# S7CAS-PLEIADES-CARTE-MERE_P06_DDR3.net
KiCad netlist of a schematic drawn in Altium Designer
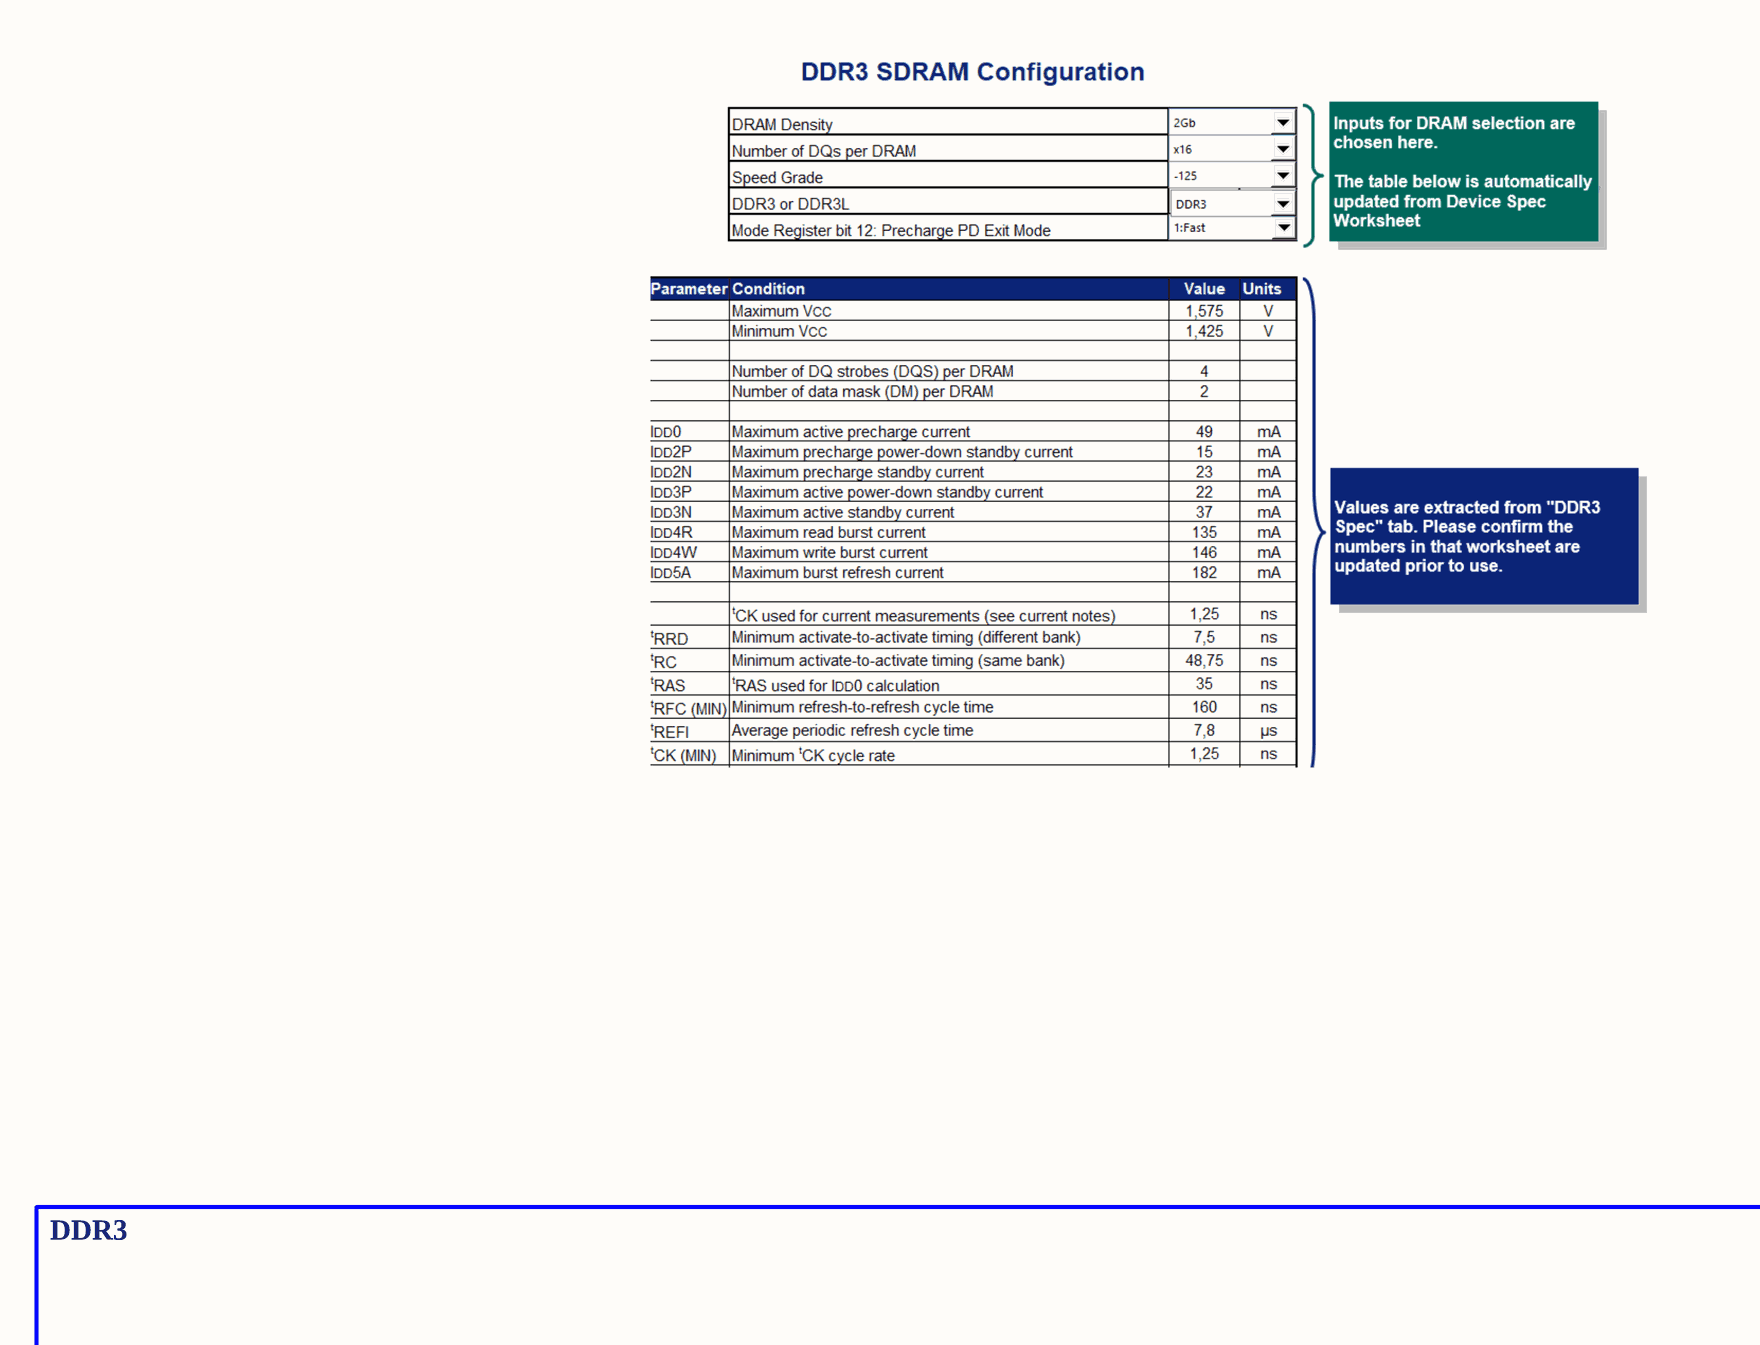
[diagram p0: S7CAS-PLEIADES-CARTE-MERE_P06_DDR3.SCHDOC, top left]
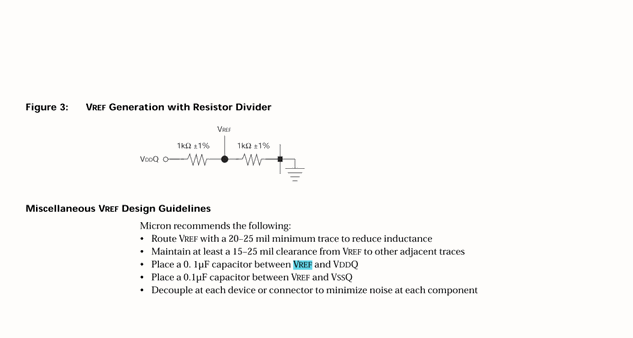
[diagram p1: S7CAS-PLEIADES-CARTE-MERE_P06_DDR3.SCHDOC, top right]
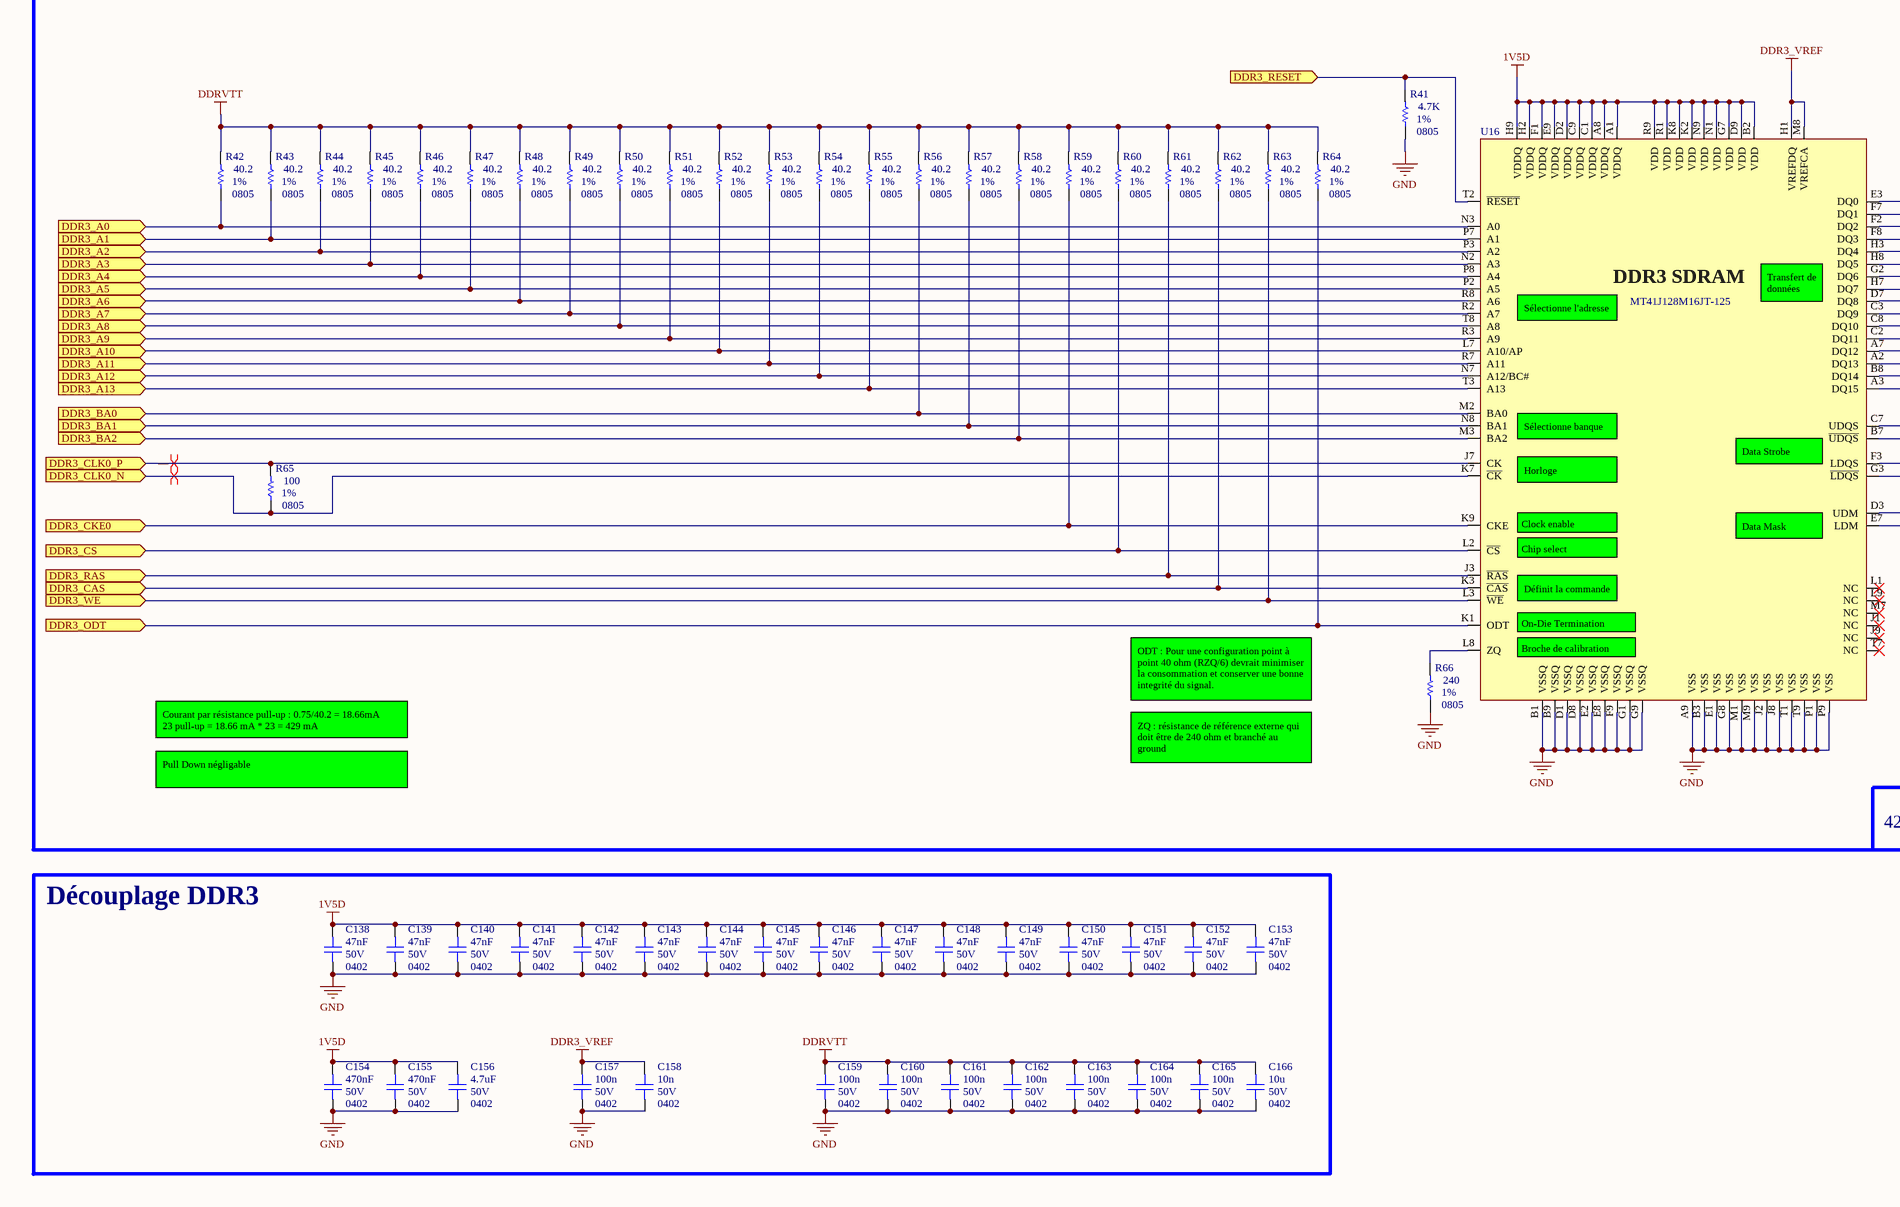
[diagram p2: S7CAS-PLEIADES-CARTE-MERE_P06_DDR3.SCHDOC, bottom left]
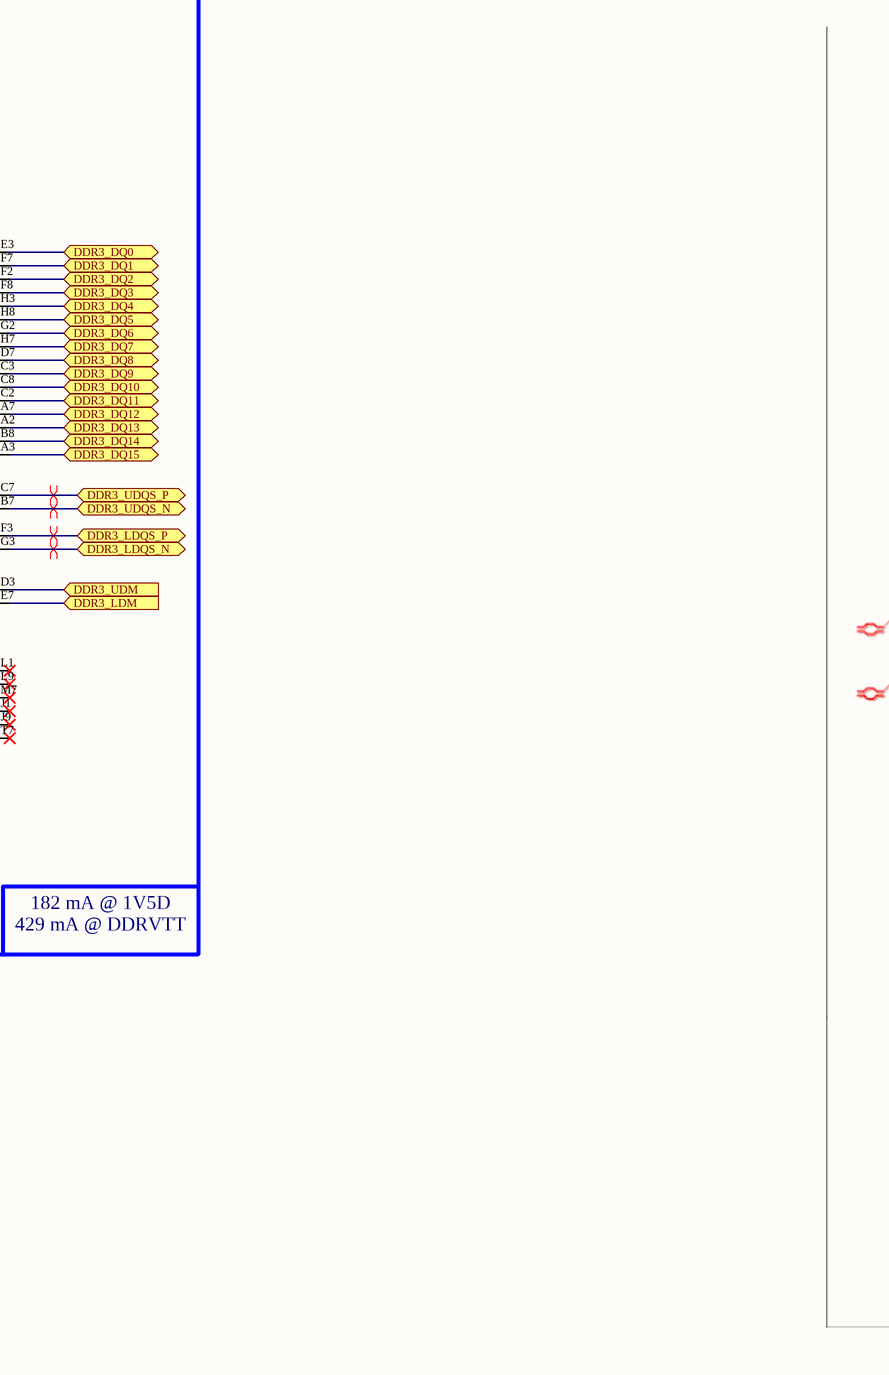
[diagram p3: S7CAS-PLEIADES-CARTE-MERE_P06_DDR3.SCHDOC, bottom middle]
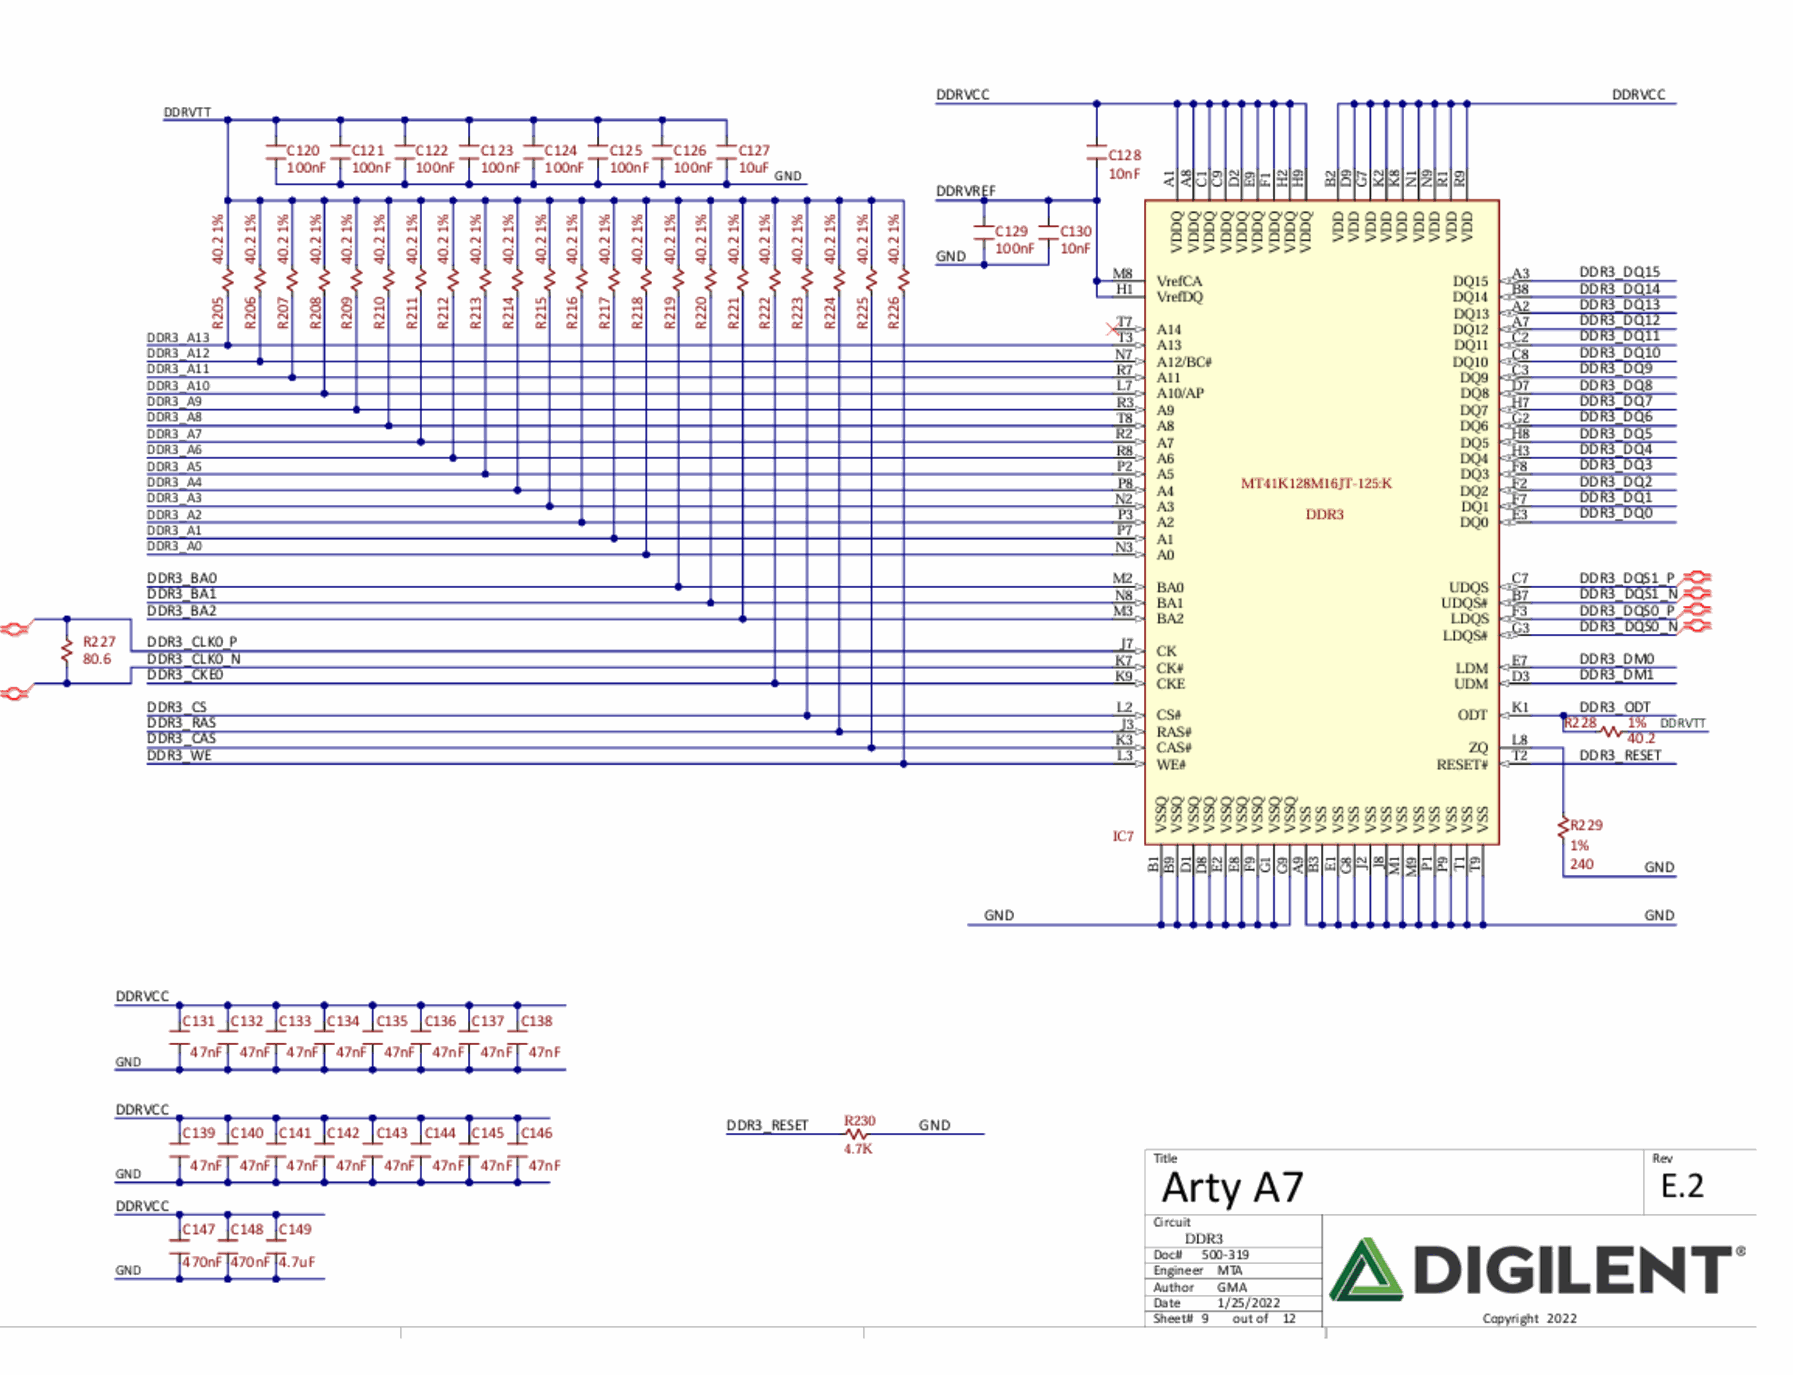
[diagram p4: S7CAS-PLEIADES-CARTE-MERE_P06_DDR3.SCHDOC, bottom right]

(export (version "E")
  (design (tool "Eeschema 10.0.6"))
  (components
    (comp (ref "C138")
      (value "47nF")
      (footprint "CAP_0402")
      (description "CAP - 0402")
      (fields
        (field (name "VOLTAGE") "50V")
        (field (name "PACKAGE") "0402")
        (field (name "CREATEDBY") "Jonathan Bouchard")
      )
      (libsource (lib "s7cas_lib2023") (part "CAP - 0402"))
    )
    (comp (ref "C139")
      (value "47nF")
      (footprint "CAP_0402")
      (description "CAP - 0402")
      (fields
        (field (name "VOLTAGE") "50V")
        (field (name "PACKAGE") "0402")
        (field (name "CREATEDBY") "Jonathan Bouchard")
      )
      (libsource (lib "s7cas_lib2023") (part "CAP - 0402"))
    )
    (comp (ref "C140")
      (value "47nF")
      (footprint "CAP_0402")
      (description "CAP - 0402")
      (fields
        (field (name "VOLTAGE") "50V")
        (field (name "PACKAGE") "0402")
        (field (name "CREATEDBY") "Jonathan Bouchard")
      )
      (libsource (lib "s7cas_lib2023") (part "CAP - 0402"))
    )
    (comp (ref "C141")
      (value "47nF")
      (footprint "CAP_0402")
      (description "CAP - 0402")
      (fields
        (field (name "VOLTAGE") "50V")
        (field (name "PACKAGE") "0402")
        (field (name "CREATEDBY") "Jonathan Bouchard")
      )
      (libsource (lib "s7cas_lib2023") (part "CAP - 0402"))
    )
    (comp (ref "C142")
      (value "47nF")
      (footprint "CAP_0402")
      (description "CAP - 0402")
      (fields
        (field (name "VOLTAGE") "50V")
        (field (name "PACKAGE") "0402")
        (field (name "CREATEDBY") "Jonathan Bouchard")
      )
      (libsource (lib "s7cas_lib2023") (part "CAP - 0402"))
    )
    (comp (ref "C143")
      (value "47nF")
      (footprint "CAP_0402")
      (description "CAP - 0402")
      (fields
        (field (name "VOLTAGE") "50V")
        (field (name "PACKAGE") "0402")
        (field (name "CREATEDBY") "Jonathan Bouchard")
      )
      (libsource (lib "s7cas_lib2023") (part "CAP - 0402"))
    )
    (comp (ref "C144")
      (value "47nF")
      (footprint "CAP_0402")
      (description "CAP - 0402")
      (fields
        (field (name "VOLTAGE") "50V")
        (field (name "PACKAGE") "0402")
        (field (name "CREATEDBY") "Jonathan Bouchard")
      )
      (libsource (lib "s7cas_lib2023") (part "CAP - 0402"))
    )
    (comp (ref "C145")
      (value "47nF")
      (footprint "CAP_0402")
      (description "CAP - 0402")
      (fields
        (field (name "VOLTAGE") "50V")
        (field (name "PACKAGE") "0402")
        (field (name "CREATEDBY") "Jonathan Bouchard")
      )
      (libsource (lib "s7cas_lib2023") (part "CAP - 0402"))
    )
    (comp (ref "C146")
      (value "47nF")
      (footprint "CAP_0402")
      (description "CAP - 0402")
      (fields
        (field (name "VOLTAGE") "50V")
        (field (name "PACKAGE") "0402")
        (field (name "CREATEDBY") "Jonathan Bouchard")
      )
      (libsource (lib "s7cas_lib2023") (part "CAP - 0402"))
    )
    (comp (ref "C147")
      (value "47nF")
      (footprint "CAP_0402")
      (description "CAP - 0402")
      (fields
        (field (name "VOLTAGE") "50V")
        (field (name "PACKAGE") "0402")
        (field (name "CREATEDBY") "Jonathan Bouchard")
      )
      (libsource (lib "s7cas_lib2023") (part "CAP - 0402"))
    )
    (comp (ref "C148")
      (value "47nF")
      (footprint "CAP_0402")
      (description "CAP - 0402")
      (fields
        (field (name "VOLTAGE") "50V")
        (field (name "PACKAGE") "0402")
        (field (name "CREATEDBY") "Jonathan Bouchard")
      )
      (libsource (lib "s7cas_lib2023") (part "CAP - 0402"))
    )
    (comp (ref "C149")
      (value "47nF")
      (footprint "CAP_0402")
      (description "CAP - 0402")
      (fields
        (field (name "VOLTAGE") "50V")
        (field (name "PACKAGE") "0402")
        (field (name "CREATEDBY") "Jonathan Bouchard")
      )
      (libsource (lib "s7cas_lib2023") (part "CAP - 0402"))
    )
    (comp (ref "C150")
      (value "47nF")
      (footprint "CAP_0402")
      (description "CAP - 0402")
      (fields
        (field (name "VOLTAGE") "50V")
        (field (name "PACKAGE") "0402")
        (field (name "CREATEDBY") "Jonathan Bouchard")
      )
      (libsource (lib "s7cas_lib2023") (part "CAP - 0402"))
    )
    (comp (ref "C151")
      (value "47nF")
      (footprint "CAP_0402")
      (description "CAP - 0402")
      (fields
        (field (name "VOLTAGE") "50V")
        (field (name "PACKAGE") "0402")
        (field (name "CREATEDBY") "Jonathan Bouchard")
      )
      (libsource (lib "s7cas_lib2023") (part "CAP - 0402"))
    )
    (comp (ref "C152")
      (value "47nF")
      (footprint "CAP_0402")
      (description "CAP - 0402")
      (fields
        (field (name "VOLTAGE") "50V")
        (field (name "PACKAGE") "0402")
        (field (name "CREATEDBY") "Jonathan Bouchard")
      )
      (libsource (lib "s7cas_lib2023") (part "CAP - 0402"))
    )
    (comp (ref "C153")
      (value "47nF")
      (footprint "CAP_0402")
      (description "CAP - 0402")
      (fields
        (field (name "VOLTAGE") "50V")
        (field (name "PACKAGE") "0402")
        (field (name "CREATEDBY") "Jonathan Bouchard")
      )
      (libsource (lib "s7cas_lib2023") (part "CAP - 0402"))
    )
    (comp (ref "C154")
      (value "470nF")
      (footprint "CAP_0402")
      (description "CAP - 0402")
      (fields
        (field (name "VOLTAGE") "50V")
        (field (name "PACKAGE") "0402")
        (field (name "CREATEDBY") "Jonathan Bouchard")
      )
      (libsource (lib "s7cas_lib2023") (part "CAP - 0402"))
    )
    (comp (ref "C155")
      (value "470nF")
      (footprint "CAP_0402")
      (description "CAP - 0402")
      (fields
        (field (name "VOLTAGE") "50V")
        (field (name "PACKAGE") "0402")
        (field (name "CREATEDBY") "Jonathan Bouchard")
      )
      (libsource (lib "s7cas_lib2023") (part "CAP - 0402"))
    )
    (comp (ref "C156")
      (value "4.7uF")
      (footprint "CAP_0402")
      (description "CAP - 0402")
      (fields
        (field (name "VOLTAGE") "50V")
        (field (name "PACKAGE") "0402")
        (field (name "CREATEDBY") "Jonathan Bouchard")
      )
      (libsource (lib "s7cas_lib2023") (part "CAP - 0402"))
    )
    (comp (ref "C157")
      (value "100n")
      (footprint "CAP_0402")
      (description "CAP - 0402")
      (fields
        (field (name "VOLTAGE") "50V")
        (field (name "PACKAGE") "0402")
        (field (name "CREATEDBY") "Jonathan Bouchard")
      )
      (libsource (lib "s7cas_lib2023") (part "CAP - 0402"))
    )
    (comp (ref "C158")
      (value "10n")
      (footprint "CAP_0402")
      (description "CAP - 0402")
      (fields
        (field (name "VOLTAGE") "50V")
        (field (name "PACKAGE") "0402")
        (field (name "CREATEDBY") "Jonathan Bouchard")
      )
      (libsource (lib "s7cas_lib2023") (part "CAP - 0402"))
    )
    (comp (ref "C159")
      (value "100n")
      (footprint "CAP_0402")
      (description "CAP - 0402")
      (fields
        (field (name "VOLTAGE") "50V")
        (field (name "PACKAGE") "0402")
        (field (name "CREATEDBY") "Jonathan Bouchard")
      )
      (libsource (lib "s7cas_lib2023") (part "CAP - 0402"))
    )
    (comp (ref "C160")
      (value "100n")
      (footprint "CAP_0402")
      (description "CAP - 0402")
      (fields
        (field (name "VOLTAGE") "50V")
        (field (name "PACKAGE") "0402")
        (field (name "CREATEDBY") "Jonathan Bouchard")
      )
      (libsource (lib "s7cas_lib2023") (part "CAP - 0402"))
    )
    (comp (ref "C161")
      (value "100n")
      (footprint "CAP_0402")
      (description "CAP - 0402")
      (fields
        (field (name "VOLTAGE") "50V")
        (field (name "PACKAGE") "0402")
        (field (name "CREATEDBY") "Jonathan Bouchard")
      )
      (libsource (lib "s7cas_lib2023") (part "CAP - 0402"))
    )
    (comp (ref "C162")
      (value "100n")
      (footprint "CAP_0402")
      (description "CAP - 0402")
      (fields
        (field (name "VOLTAGE") "50V")
        (field (name "PACKAGE") "0402")
        (field (name "CREATEDBY") "Jonathan Bouchard")
      )
      (libsource (lib "s7cas_lib2023") (part "CAP - 0402"))
    )
    (comp (ref "C163")
      (value "100n")
      (footprint "CAP_0402")
      (description "CAP - 0402")
      (fields
        (field (name "VOLTAGE") "50V")
        (field (name "PACKAGE") "0402")
        (field (name "CREATEDBY") "Jonathan Bouchard")
      )
      (libsource (lib "s7cas_lib2023") (part "CAP - 0402"))
    )
    (comp (ref "C164")
      (value "100n")
      (footprint "CAP_0402")
      (description "CAP - 0402")
      (fields
        (field (name "VOLTAGE") "50V")
        (field (name "PACKAGE") "0402")
        (field (name "CREATEDBY") "Jonathan Bouchard")
      )
      (libsource (lib "s7cas_lib2023") (part "CAP - 0402"))
    )
    (comp (ref "C165")
      (value "100n")
      (footprint "CAP_0402")
      (description "CAP - 0402")
      (fields
        (field (name "VOLTAGE") "50V")
        (field (name "PACKAGE") "0402")
        (field (name "CREATEDBY") "Jonathan Bouchard")
      )
      (libsource (lib "s7cas_lib2023") (part "CAP - 0402"))
    )
    (comp (ref "C166")
      (value "10u")
      (footprint "CAP_0402")
      (description "CAP - 0402")
      (fields
        (field (name "VOLTAGE") "50V")
        (field (name "PACKAGE") "0402")
        (field (name "CREATEDBY") "Jonathan Bouchard")
      )
      (libsource (lib "s7cas_lib2023") (part "CAP - 0402"))
    )
    (comp (ref "R41")
      (value "4.7K")
      (footprint "RES_0805")
      (description "RES - 0805")
      (fields
        (field (name "PACKAGE") "0805")
        (field (name "PRECISION") "1%")
        (field (name "CREATEDBY") "Jonathan Bouchard")
      )
      (libsource (lib "s7cas_lib2023") (part "RES - 0805"))
    )
    (comp (ref "R42")
      (value "40.2")
      (footprint "RES_0805")
      (description "RES - 0805")
      (fields
        (field (name "PACKAGE") "0805")
        (field (name "PRECISION") "1%")
        (field (name "CREATEDBY") "Jonathan Bouchard")
      )
      (libsource (lib "s7cas_lib2023") (part "RES - 0805"))
    )
    (comp (ref "R43")
      (value "40.2")
      (footprint "RES_0805")
      (description "RES - 0805")
      (fields
        (field (name "PACKAGE") "0805")
        (field (name "PRECISION") "1%")
        (field (name "CREATEDBY") "Jonathan Bouchard")
      )
      (libsource (lib "s7cas_lib2023") (part "RES - 0805"))
    )
    (comp (ref "R44")
      (value "40.2")
      (footprint "RES_0805")
      (description "RES - 0805")
      (fields
        (field (name "PACKAGE") "0805")
        (field (name "PRECISION") "1%")
        (field (name "CREATEDBY") "Jonathan Bouchard")
      )
      (libsource (lib "s7cas_lib2023") (part "RES - 0805"))
    )
    (comp (ref "R45")
      (value "40.2")
      (footprint "RES_0805")
      (description "RES - 0805")
      (fields
        (field (name "PACKAGE") "0805")
        (field (name "PRECISION") "1%")
        (field (name "CREATEDBY") "Jonathan Bouchard")
      )
      (libsource (lib "s7cas_lib2023") (part "RES - 0805"))
    )
    (comp (ref "R46")
      (value "40.2")
      (footprint "RES_0805")
      (description "RES - 0805")
      (fields
        (field (name "PACKAGE") "0805")
        (field (name "PRECISION") "1%")
        (field (name "CREATEDBY") "Jonathan Bouchard")
      )
      (libsource (lib "s7cas_lib2023") (part "RES - 0805"))
    )
    (comp (ref "R47")
      (value "40.2")
      (footprint "RES_0805")
      (description "RES - 0805")
      (fields
        (field (name "PACKAGE") "0805")
        (field (name "PRECISION") "1%")
        (field (name "CREATEDBY") "Jonathan Bouchard")
      )
      (libsource (lib "s7cas_lib2023") (part "RES - 0805"))
    )
    (comp (ref "R48")
      (value "40.2")
      (footprint "RES_0805")
      (description "RES - 0805")
      (fields
        (field (name "PACKAGE") "0805")
        (field (name "PRECISION") "1%")
        (field (name "CREATEDBY") "Jonathan Bouchard")
      )
      (libsource (lib "s7cas_lib2023") (part "RES - 0805"))
    )
    (comp (ref "R49")
      (value "40.2")
      (footprint "RES_0805")
      (description "RES - 0805")
      (fields
        (field (name "PACKAGE") "0805")
        (field (name "PRECISION") "1%")
        (field (name "CREATEDBY") "Jonathan Bouchard")
      )
      (libsource (lib "s7cas_lib2023") (part "RES - 0805"))
    )
    (comp (ref "R50")
      (value "40.2")
      (footprint "RES_0805")
      (description "RES - 0805")
      (fields
        (field (name "PACKAGE") "0805")
        (field (name "PRECISION") "1%")
        (field (name "CREATEDBY") "Jonathan Bouchard")
      )
      (libsource (lib "s7cas_lib2023") (part "RES - 0805"))
    )
    (comp (ref "R51")
      (value "40.2")
      (footprint "RES_0805")
      (description "RES - 0805")
      (fields
        (field (name "PACKAGE") "0805")
        (field (name "PRECISION") "1%")
        (field (name "CREATEDBY") "Jonathan Bouchard")
      )
      (libsource (lib "s7cas_lib2023") (part "RES - 0805"))
    )
    (comp (ref "R52")
      (value "40.2")
      (footprint "RES_0805")
      (description "RES - 0805")
      (fields
        (field (name "PACKAGE") "0805")
        (field (name "PRECISION") "1%")
        (field (name "CREATEDBY") "Jonathan Bouchard")
      )
      (libsource (lib "s7cas_lib2023") (part "RES - 0805"))
    )
    (comp (ref "R53")
      (value "40.2")
      (footprint "RES_0805")
      (description "RES - 0805")
      (fields
        (field (name "PACKAGE") "0805")
        (field (name "PRECISION") "1%")
        (field (name "CREATEDBY") "Jonathan Bouchard")
      )
      (libsource (lib "s7cas_lib2023") (part "RES - 0805"))
    )
    (comp (ref "R54")
      (value "40.2")
      (footprint "RES_0805")
      (description "RES - 0805")
      (fields
        (field (name "PACKAGE") "0805")
        (field (name "PRECISION") "1%")
        (field (name "CREATEDBY") "Jonathan Bouchard")
      )
      (libsource (lib "s7cas_lib2023") (part "RES - 0805"))
    )
    (comp (ref "R55")
      (value "40.2")
      (footprint "RES_0805")
      (description "RES - 0805")
      (fields
        (field (name "PACKAGE") "0805")
        (field (name "PRECISION") "1%")
        (field (name "CREATEDBY") "Jonathan Bouchard")
      )
      (libsource (lib "s7cas_lib2023") (part "RES - 0805"))
    )
    (comp (ref "R56")
      (value "40.2")
      (footprint "RES_0805")
      (description "RES - 0805")
      (fields
        (field (name "PACKAGE") "0805")
        (field (name "PRECISION") "1%")
        (field (name "CREATEDBY") "Jonathan Bouchard")
      )
      (libsource (lib "s7cas_lib2023") (part "RES - 0805"))
    )
    (comp (ref "R57")
      (value "40.2")
      (footprint "RES_0805")
      (description "RES - 0805")
      (fields
        (field (name "PACKAGE") "0805")
        (field (name "PRECISION") "1%")
        (field (name "CREATEDBY") "Jonathan Bouchard")
      )
      (libsource (lib "s7cas_lib2023") (part "RES - 0805"))
    )
    (comp (ref "R58")
      (value "40.2")
      (footprint "RES_0805")
      (description "RES - 0805")
      (fields
        (field (name "PACKAGE") "0805")
        (field (name "PRECISION") "1%")
        (field (name "CREATEDBY") "Jonathan Bouchard")
      )
      (libsource (lib "s7cas_lib2023") (part "RES - 0805"))
    )
    (comp (ref "R59")
      (value "40.2")
      (footprint "RES_0805")
      (description "RES - 0805")
      (fields
        (field (name "PACKAGE") "0805")
        (field (name "PRECISION") "1%")
        (field (name "CREATEDBY") "Jonathan Bouchard")
      )
      (libsource (lib "s7cas_lib2023") (part "RES - 0805"))
    )
    (comp (ref "R60")
      (value "40.2")
      (footprint "RES_0805")
      (description "RES - 0805")
      (fields
        (field (name "PACKAGE") "0805")
        (field (name "PRECISION") "1%")
        (field (name "CREATEDBY") "Jonathan Bouchard")
      )
      (libsource (lib "s7cas_lib2023") (part "RES - 0805"))
    )
    (comp (ref "R61")
      (value "40.2")
      (footprint "RES_0805")
      (description "RES - 0805")
      (fields
        (field (name "PACKAGE") "0805")
        (field (name "PRECISION") "1%")
        (field (name "CREATEDBY") "Jonathan Bouchard")
      )
      (libsource (lib "s7cas_lib2023") (part "RES - 0805"))
    )
    (comp (ref "R62")
      (value "40.2")
      (footprint "RES_0805")
      (description "RES - 0805")
      (fields
        (field (name "PACKAGE") "0805")
        (field (name "PRECISION") "1%")
        (field (name "CREATEDBY") "Jonathan Bouchard")
      )
      (libsource (lib "s7cas_lib2023") (part "RES - 0805"))
    )
    (comp (ref "R63")
      (value "40.2")
      (footprint "RES_0805")
      (description "RES - 0805")
      (fields
        (field (name "PACKAGE") "0805")
        (field (name "PRECISION") "1%")
        (field (name "CREATEDBY") "Jonathan Bouchard")
      )
      (libsource (lib "s7cas_lib2023") (part "RES - 0805"))
    )
    (comp (ref "R64")
      (value "40.2")
      (footprint "RES_0805")
      (description "RES - 0805")
      (fields
        (field (name "PACKAGE") "0805")
        (field (name "PRECISION") "1%")
        (field (name "CREATEDBY") "Jonathan Bouchard")
      )
      (libsource (lib "s7cas_lib2023") (part "RES - 0805"))
    )
    (comp (ref "R65")
      (value "100")
      (footprint "RES_0805")
      (description "RES - 0805")
      (fields
        (field (name "PACKAGE") "0805")
        (field (name "PRECISION") "1%")
        (field (name "CREATEDBY") "Jonathan Bouchard")
      )
      (libsource (lib "s7cas_lib2023") (part "RES - 0805"))
    )
    (comp (ref "R66")
      (value "240")
      (footprint "RES_0805")
      (description "RES - 0805")
      (fields
        (field (name "PACKAGE") "0805")
        (field (name "PRECISION") "1%")
        (field (name "CREATEDBY") "Jonathan Bouchard")
      )
      (libsource (lib "s7cas_lib2023") (part "RES - 0805"))
    )
    (comp (ref "U16")
      (value "MT41J128M16JT-125")
      (footprint "MEM_DDR3_MT41J128M16JT-125")
      (description "MEM - DDR3 SDRAM 2GBIT 800MHZ - TFBGA-96")
      (fields
        (field (name "VOLTAGE") "1.425 V ~ 1.575 V")
        (field (name "MFG") "Micrel")
        (field (name "CREATEDBY") "Jonathan Bouchard")
      )
      (libsource (lib "s7cas_lib2023") (part "MEM_DDR3_MT41J128M16JT-125{colon}K TR"))
    )
  )
  (nets
    (net (code "1") (name "/DDR3_A0") (class "Default")
      (node (ref "R42") (pin "1") (pinfunction "1_1") (pintype "passive"))
      (node (ref "U16") (pin "N3") (pinfunction "A0_N3") (pintype "passive"))
    )
    (net (code "2") (name "/DDR3_A1") (class "Default")
      (node (ref "R43") (pin "1") (pinfunction "1_1") (pintype "passive"))
      (node (ref "U16") (pin "P7") (pinfunction "A1_P7") (pintype "passive"))
    )
    (net (code "3") (name "/DDR3_A2") (class "Default")
      (node (ref "R44") (pin "1") (pinfunction "1_1") (pintype "passive"))
      (node (ref "U16") (pin "P3") (pinfunction "A2_P3") (pintype "passive"))
    )
    (net (code "4") (name "/DDR3_A3") (class "Default")
      (node (ref "R45") (pin "1") (pinfunction "1_1") (pintype "passive"))
      (node (ref "U16") (pin "N2") (pinfunction "A3_N2") (pintype "passive"))
    )
    (net (code "5") (name "/DDR3_A4") (class "Default")
      (node (ref "R46") (pin "1") (pinfunction "1_1") (pintype "passive"))
      (node (ref "U16") (pin "P8") (pinfunction "A4_P8") (pintype "passive"))
    )
    (net (code "6") (name "/DDR3_A5") (class "Default")
      (node (ref "R47") (pin "1") (pinfunction "1_1") (pintype "passive"))
      (node (ref "U16") (pin "P2") (pinfunction "A5_P2") (pintype "passive"))
    )
    (net (code "7") (name "/DDR3_A6") (class "Default")
      (node (ref "R48") (pin "1") (pinfunction "1_1") (pintype "passive"))
      (node (ref "U16") (pin "R8") (pinfunction "A6_R8") (pintype "passive"))
    )
    (net (code "8") (name "/DDR3_A7") (class "Default")
      (node (ref "R49") (pin "1") (pinfunction "1_1") (pintype "passive"))
      (node (ref "U16") (pin "R2") (pinfunction "A7_R2") (pintype "passive"))
    )
    (net (code "9") (name "/DDR3_A8") (class "Default")
      (node (ref "R50") (pin "1") (pinfunction "1_1") (pintype "passive"))
      (node (ref "U16") (pin "T8") (pinfunction "A8_T8") (pintype "passive"))
    )
    (net (code "10") (name "/DDR3_A9") (class "Default")
      (node (ref "R51") (pin "1") (pinfunction "1_1") (pintype "passive"))
      (node (ref "U16") (pin "R3") (pinfunction "A9_R3") (pintype "passive"))
    )
    (net (code "11") (name "/DDR3_A10") (class "Default")
      (node (ref "R52") (pin "1") (pinfunction "1_1") (pintype "passive"))
      (node (ref "U16") (pin "L7") (pinfunction "A10/AP_L7") (pintype "passive"))
    )
    (net (code "12") (name "/DDR3_A11") (class "Default")
      (node (ref "R53") (pin "1") (pinfunction "1_1") (pintype "passive"))
      (node (ref "U16") (pin "R7") (pinfunction "A11_R7") (pintype "passive"))
    )
    (net (code "13") (name "/DDR3_A12") (class "Default")
      (node (ref "R54") (pin "1") (pinfunction "1_1") (pintype "passive"))
      (node (ref "U16") (pin "N7") (pinfunction "A12/BC#_N7") (pintype "passive"))
    )
    (net (code "14") (name "/DDR3_A13") (class "Default")
      (node (ref "R55") (pin "1") (pinfunction "1_1") (pintype "passive"))
      (node (ref "U16") (pin "T3") (pinfunction "A13_T3") (pintype "passive"))
    )
    (net (code "15") (name "/DDR3_BA0") (class "Default")
      (node (ref "R56") (pin "1") (pinfunction "1_1") (pintype "passive"))
      (node (ref "U16") (pin "M2") (pinfunction "BA0_M2") (pintype "passive"))
    )
    (net (code "16") (name "/DDR3_BA1") (class "Default")
      (node (ref "R57") (pin "1") (pinfunction "1_1") (pintype "passive"))
      (node (ref "U16") (pin "N8") (pinfunction "BA1_N8") (pintype "passive"))
    )
    (net (code "17") (name "/DDR3_BA2") (class "Default")
      (node (ref "R58") (pin "1") (pinfunction "1_1") (pintype "passive"))
      (node (ref "U16") (pin "M3") (pinfunction "BA2_M3") (pintype "passive"))
    )
    (net (code "18") (name "/DDR3_CAS") (class "Default")
      (node (ref "R62") (pin "1") (pinfunction "1_1") (pintype "passive"))
      (node (ref "U16") (pin "K3") (pinfunction "CAS_K3") (pintype "passive"))
    )
    (net (code "19") (name "/DDR3_CKE0") (class "Default")
      (node (ref "R59") (pin "1") (pinfunction "1_1") (pintype "passive"))
      (node (ref "U16") (pin "K9") (pinfunction "CKE_K9") (pintype "passive"))
    )
    (net (code "20") (name "/DDR3_CLK0_N") (class "Default")
      (node (ref "R65") (pin "1") (pinfunction "1_1") (pintype "passive"))
      (node (ref "U16") (pin "K7") (pinfunction "CK_K7") (pintype "passive"))
    )
    (net (code "21") (name "/DDR3_CLK0_P") (class "Default")
      (node (ref "R65") (pin "2") (pinfunction "2_2") (pintype "passive"))
      (node (ref "U16") (pin "J7") (pinfunction "CK_J7") (pintype "passive"))
    )
    (net (code "22") (name "/DDR3_CS") (class "Default")
      (node (ref "R60") (pin "1") (pinfunction "1_1") (pintype "passive"))
      (node (ref "U16") (pin "L2") (pinfunction "CS_L2") (pintype "passive"))
    )
    (net (code "23") (name "/DDR3_DQ0") (class "Default")
      (node (ref "U16") (pin "E3") (pinfunction "DQ0_E3") (pintype "passive"))
    )
    (net (code "24") (name "/DDR3_DQ1") (class "Default")
      (node (ref "U16") (pin "F7") (pinfunction "DQ1_F7") (pintype "passive"))
    )
    (net (code "25") (name "/DDR3_DQ2") (class "Default")
      (node (ref "U16") (pin "F2") (pinfunction "DQ2_F2") (pintype "passive"))
    )
    (net (code "26") (name "/DDR3_DQ3") (class "Default")
      (node (ref "U16") (pin "F8") (pinfunction "DQ3_F8") (pintype "passive"))
    )
    (net (code "27") (name "/DDR3_DQ4") (class "Default")
      (node (ref "U16") (pin "H3") (pinfunction "DQ4_H3") (pintype "passive"))
    )
    (net (code "28") (name "/DDR3_DQ5") (class "Default")
      (node (ref "U16") (pin "H8") (pinfunction "DQ5_H8") (pintype "passive"))
    )
    (net (code "29") (name "/DDR3_DQ6") (class "Default")
      (node (ref "U16") (pin "G2") (pinfunction "DQ6_G2") (pintype "passive"))
    )
    (net (code "30") (name "/DDR3_DQ7") (class "Default")
      (node (ref "U16") (pin "H7") (pinfunction "DQ7_H7") (pintype "passive"))
    )
    (net (code "31") (name "/DDR3_DQ8") (class "Default")
      (node (ref "U16") (pin "D7") (pinfunction "DQ8_D7") (pintype "passive"))
    )
    (net (code "32") (name "/DDR3_DQ9") (class "Default")
      (node (ref "U16") (pin "C3") (pinfunction "DQ9_C3") (pintype "passive"))
    )
    (net (code "33") (name "/DDR3_DQ10") (class "Default")
      (node (ref "U16") (pin "C8") (pinfunction "DQ10_C8") (pintype "passive"))
    )
    (net (code "34") (name "/DDR3_DQ11") (class "Default")
      (node (ref "U16") (pin "C2") (pinfunction "DQ11_C2") (pintype "passive"))
    )
    (net (code "35") (name "/DDR3_DQ12") (class "Default")
      (node (ref "U16") (pin "A7") (pinfunction "DQ12_A7") (pintype "passive"))
    )
    (net (code "36") (name "/DDR3_DQ13") (class "Default")
      (node (ref "U16") (pin "A2") (pinfunction "DQ13_A2") (pintype "passive"))
    )
    (net (code "37") (name "/DDR3_DQ14") (class "Default")
      (node (ref "U16") (pin "B8") (pinfunction "DQ14_B8") (pintype "passive"))
    )
    (net (code "38") (name "/DDR3_DQ15") (class "Default")
      (node (ref "U16") (pin "A3") (pinfunction "DQ15_A3") (pintype "passive"))
    )
    (net (code "39") (name "/DDR3_LDM") (class "Default")
      (node (ref "U16") (pin "E7") (pinfunction "LDM_E7") (pintype "passive"))
    )
    (net (code "40") (name "/DDR3_LDQS_N") (class "Default")
      (node (ref "U16") (pin "G3") (pinfunction "LDQS_G3") (pintype "passive"))
    )
    (net (code "41") (name "/DDR3_LDQS_P") (class "Default")
      (node (ref "U16") (pin "F3") (pinfunction "LDQS_F3") (pintype "passive"))
    )
    (net (code "42") (name "/DDR3_ODT") (class "Default")
      (node (ref "R64") (pin "1") (pinfunction "1_1") (pintype "passive"))
      (node (ref "U16") (pin "K1") (pinfunction "ODT_K1") (pintype "passive"))
    )
    (net (code "43") (name "/DDR3_RAS") (class "Default")
      (node (ref "R61") (pin "1") (pinfunction "1_1") (pintype "passive"))
      (node (ref "U16") (pin "J3") (pinfunction "RAS_J3") (pintype "passive"))
    )
    (net (code "44") (name "/DDR3_RESET") (class "Default")
      (node (ref "R41") (pin "2") (pinfunction "2_2") (pintype "passive"))
      (node (ref "U16") (pin "T2") (pinfunction "RESET_T2") (pintype "passive"))
    )
    (net (code "45") (name "/DDR3_UDM") (class "Default")
      (node (ref "U16") (pin "D3") (pinfunction "UDM_D3") (pintype "passive"))
    )
    (net (code "46") (name "/DDR3_UDQS_N") (class "Default")
      (node (ref "U16") (pin "B7") (pinfunction "UDQS_B7") (pintype "passive"))
    )
    (net (code "47") (name "/DDR3_UDQS_P") (class "Default")
      (node (ref "U16") (pin "C7") (pinfunction "UDQS_C7") (pintype "passive"))
    )
    (net (code "48") (name "/DDR3_WE") (class "Default")
      (node (ref "R63") (pin "1") (pinfunction "1_1") (pintype "passive"))
      (node (ref "U16") (pin "L3") (pinfunction "WE_L3") (pintype "passive"))
    )
    (net (code "49") (name "1V5D") (class "Default")
      (node (ref "C138") (pin "2") (pinfunction "2_2") (pintype "passive"))
      (node (ref "C139") (pin "2") (pinfunction "2_2") (pintype "passive"))
      (node (ref "C140") (pin "2") (pinfunction "2_2") (pintype "passive"))
      (node (ref "C141") (pin "2") (pinfunction "2_2") (pintype "passive"))
      (node (ref "C142") (pin "2") (pinfunction "2_2") (pintype "passive"))
      (node (ref "C143") (pin "2") (pinfunction "2_2") (pintype "passive"))
      (node (ref "C144") (pin "2") (pinfunction "2_2") (pintype "passive"))
      (node (ref "C145") (pin "2") (pinfunction "2_2") (pintype "passive"))
      (node (ref "C146") (pin "2") (pinfunction "2_2") (pintype "passive"))
      (node (ref "C147") (pin "2") (pinfunction "2_2") (pintype "passive"))
      (node (ref "C148") (pin "2") (pinfunction "2_2") (pintype "passive"))
      (node (ref "C149") (pin "2") (pinfunction "2_2") (pintype "passive"))
      (node (ref "C150") (pin "2") (pinfunction "2_2") (pintype "passive"))
      (node (ref "C151") (pin "2") (pinfunction "2_2") (pintype "passive"))
      (node (ref "C152") (pin "2") (pinfunction "2_2") (pintype "passive"))
      (node (ref "C153") (pin "2") (pinfunction "2_2") (pintype "passive"))
      (node (ref "C154") (pin "2") (pinfunction "2_2") (pintype "passive"))
      (node (ref "C155") (pin "2") (pinfunction "2_2") (pintype "passive"))
      (node (ref "C156") (pin "2") (pinfunction "2_2") (pintype "passive"))
      (node (ref "U16") (pin "A1") (pinfunction "VDDQ_A1") (pintype "passive"))
      (node (ref "U16") (pin "A8") (pinfunction "VDDQ_A8") (pintype "passive"))
      (node (ref "U16") (pin "B2") (pinfunction "VDD_B2") (pintype "passive"))
      (node (ref "U16") (pin "C1") (pinfunction "VDDQ_C1") (pintype "passive"))
      (node (ref "U16") (pin "C9") (pinfunction "VDDQ_C9") (pintype "passive"))
      (node (ref "U16") (pin "D2") (pinfunction "VDDQ_D2") (pintype "passive"))
      (node (ref "U16") (pin "D9") (pinfunction "VDD_D9") (pintype "passive"))
      (node (ref "U16") (pin "E9") (pinfunction "VDDQ_E9") (pintype "passive"))
      (node (ref "U16") (pin "F1") (pinfunction "VDDQ_F1") (pintype "passive"))
      (node (ref "U16") (pin "G7") (pinfunction "VDD_G7") (pintype "passive"))
      (node (ref "U16") (pin "H2") (pinfunction "VDDQ_H2") (pintype "passive"))
      (node (ref "U16") (pin "H9") (pinfunction "VDDQ_H9") (pintype "passive"))
      (node (ref "U16") (pin "K2") (pinfunction "VDD_K2") (pintype "passive"))
      (node (ref "U16") (pin "K8") (pinfunction "VDD_K8") (pintype "passive"))
      (node (ref "U16") (pin "N1") (pinfunction "VDD_N1") (pintype "passive"))
      (node (ref "U16") (pin "N9") (pinfunction "VDD_N9") (pintype "passive"))
      (node (ref "U16") (pin "R1") (pinfunction "VDD_R1") (pintype "passive"))
      (node (ref "U16") (pin "R9") (pinfunction "VDD_R9") (pintype "passive"))
    )
    (net (code "50") (name "DDR3_VREF") (class "Default")
      (node (ref "C157") (pin "2") (pinfunction "2_2") (pintype "passive"))
      (node (ref "C158") (pin "2") (pinfunction "2_2") (pintype "passive"))
      (node (ref "U16") (pin "H1") (pinfunction "VREFDQ_H1") (pintype "passive"))
      (node (ref "U16") (pin "M8") (pinfunction "VREFCA_M8") (pintype "passive"))
    )
    (net (code "51") (name "DDRVTT") (class "Default")
      (node (ref "C159") (pin "2") (pinfunction "2_2") (pintype "passive"))
      (node (ref "C160") (pin "2") (pinfunction "2_2") (pintype "passive"))
      (node (ref "C161") (pin "2") (pinfunction "2_2") (pintype "passive"))
      (node (ref "C162") (pin "2") (pinfunction "2_2") (pintype "passive"))
      (node (ref "C163") (pin "2") (pinfunction "2_2") (pintype "passive"))
      (node (ref "C164") (pin "2") (pinfunction "2_2") (pintype "passive"))
      (node (ref "C165") (pin "2") (pinfunction "2_2") (pintype "passive"))
      (node (ref "C166") (pin "2") (pinfunction "2_2") (pintype "passive"))
      (node (ref "R42") (pin "2") (pinfunction "2_2") (pintype "passive"))
      (node (ref "R43") (pin "2") (pinfunction "2_2") (pintype "passive"))
      (node (ref "R44") (pin "2") (pinfunction "2_2") (pintype "passive"))
      (node (ref "R45") (pin "2") (pinfunction "2_2") (pintype "passive"))
      (node (ref "R46") (pin "2") (pinfunction "2_2") (pintype "passive"))
      (node (ref "R47") (pin "2") (pinfunction "2_2") (pintype "passive"))
      (node (ref "R48") (pin "2") (pinfunction "2_2") (pintype "passive"))
      (node (ref "R49") (pin "2") (pinfunction "2_2") (pintype "passive"))
      (node (ref "R50") (pin "2") (pinfunction "2_2") (pintype "passive"))
      (node (ref "R51") (pin "2") (pinfunction "2_2") (pintype "passive"))
      (node (ref "R52") (pin "2") (pinfunction "2_2") (pintype "passive"))
      (node (ref "R53") (pin "2") (pinfunction "2_2") (pintype "passive"))
      (node (ref "R54") (pin "2") (pinfunction "2_2") (pintype "passive"))
      (node (ref "R55") (pin "2") (pinfunction "2_2") (pintype "passive"))
      (node (ref "R56") (pin "2") (pinfunction "2_2") (pintype "passive"))
      (node (ref "R57") (pin "2") (pinfunction "2_2") (pintype "passive"))
      (node (ref "R58") (pin "2") (pinfunction "2_2") (pintype "passive"))
      (node (ref "R59") (pin "2") (pinfunction "2_2") (pintype "passive"))
      (node (ref "R60") (pin "2") (pinfunction "2_2") (pintype "passive"))
      (node (ref "R61") (pin "2") (pinfunction "2_2") (pintype "passive"))
      (node (ref "R62") (pin "2") (pinfunction "2_2") (pintype "passive"))
      (node (ref "R63") (pin "2") (pinfunction "2_2") (pintype "passive"))
      (node (ref "R64") (pin "2") (pinfunction "2_2") (pintype "passive"))
    )
    (net (code "52") (name "GND") (class "Default")
      (node (ref "C138") (pin "1") (pinfunction "1_1") (pintype "passive"))
      (node (ref "C139") (pin "1") (pinfunction "1_1") (pintype "passive"))
      (node (ref "C140") (pin "1") (pinfunction "1_1") (pintype "passive"))
      (node (ref "C141") (pin "1") (pinfunction "1_1") (pintype "passive"))
      (node (ref "C142") (pin "1") (pinfunction "1_1") (pintype "passive"))
      (node (ref "C143") (pin "1") (pinfunction "1_1") (pintype "passive"))
      (node (ref "C144") (pin "1") (pinfunction "1_1") (pintype "passive"))
      (node (ref "C145") (pin "1") (pinfunction "1_1") (pintype "passive"))
      (node (ref "C146") (pin "1") (pinfunction "1_1") (pintype "passive"))
      (node (ref "C147") (pin "1") (pinfunction "1_1") (pintype "passive"))
      (node (ref "C148") (pin "1") (pinfunction "1_1") (pintype "passive"))
      (node (ref "C149") (pin "1") (pinfunction "1_1") (pintype "passive"))
      (node (ref "C150") (pin "1") (pinfunction "1_1") (pintype "passive"))
      (node (ref "C151") (pin "1") (pinfunction "1_1") (pintype "passive"))
      (node (ref "C152") (pin "1") (pinfunction "1_1") (pintype "passive"))
      (node (ref "C153") (pin "1") (pinfunction "1_1") (pintype "passive"))
      (node (ref "C154") (pin "1") (pinfunction "1_1") (pintype "passive"))
      (node (ref "C155") (pin "1") (pinfunction "1_1") (pintype "passive"))
      (node (ref "C156") (pin "1") (pinfunction "1_1") (pintype "passive"))
      (node (ref "C157") (pin "1") (pinfunction "1_1") (pintype "passive"))
      (node (ref "C158") (pin "1") (pinfunction "1_1") (pintype "passive"))
      (node (ref "C159") (pin "1") (pinfunction "1_1") (pintype "passive"))
      (node (ref "C160") (pin "1") (pinfunction "1_1") (pintype "passive"))
      (node (ref "C161") (pin "1") (pinfunction "1_1") (pintype "passive"))
      (node (ref "C162") (pin "1") (pinfunction "1_1") (pintype "passive"))
      (node (ref "C163") (pin "1") (pinfunction "1_1") (pintype "passive"))
      (node (ref "C164") (pin "1") (pinfunction "1_1") (pintype "passive"))
      (node (ref "C165") (pin "1") (pinfunction "1_1") (pintype "passive"))
      (node (ref "C166") (pin "1") (pinfunction "1_1") (pintype "passive"))
      (node (ref "R41") (pin "1") (pinfunction "1_1") (pintype "passive"))
      (node (ref "R66") (pin "1") (pinfunction "1_1") (pintype "passive"))
      (node (ref "U16") (pin "A9") (pinfunction "VSS_A9") (pintype "passive"))
      (node (ref "U16") (pin "B1") (pinfunction "VSSQ_B1") (pintype "passive"))
      (node (ref "U16") (pin "B3") (pinfunction "VSS_B3") (pintype "passive"))
      (node (ref "U16") (pin "B9") (pinfunction "VSSQ_B9") (pintype "passive"))
      (node (ref "U16") (pin "D1") (pinfunction "VSSQ_D1") (pintype "passive"))
      (node (ref "U16") (pin "D8") (pinfunction "VSSQ_D8") (pintype "passive"))
      (node (ref "U16") (pin "E1") (pinfunction "VSS_E1") (pintype "passive"))
      (node (ref "U16") (pin "E2") (pinfunction "VSSQ_E2") (pintype "passive"))
      (node (ref "U16") (pin "E8") (pinfunction "VSSQ_E8") (pintype "passive"))
      (node (ref "U16") (pin "F9") (pinfunction "VSSQ_F9") (pintype "passive"))
      (node (ref "U16") (pin "G1") (pinfunction "VSSQ_G1") (pintype "passive"))
      (node (ref "U16") (pin "G8") (pinfunction "VSS_G8") (pintype "passive"))
      (node (ref "U16") (pin "G9") (pinfunction "VSSQ_G9") (pintype "passive"))
      (node (ref "U16") (pin "J2") (pinfunction "VSS_J2") (pintype "passive"))
      (node (ref "U16") (pin "J8") (pinfunction "VSS_J8") (pintype "passive"))
      (node (ref "U16") (pin "M1") (pinfunction "VSS_M1") (pintype "passive"))
      (node (ref "U16") (pin "M9") (pinfunction "VSS_M9") (pintype "passive"))
      (node (ref "U16") (pin "P1") (pinfunction "VSS_P1") (pintype "passive"))
      (node (ref "U16") (pin "P9") (pinfunction "VSS_P9") (pintype "passive"))
      (node (ref "U16") (pin "T1") (pinfunction "VSS_T1") (pintype "passive"))
      (node (ref "U16") (pin "T9") (pinfunction "VSS_T9") (pintype "passive"))
    )
    (net (code "53") (name "Net-(U16-ZQ)") (class "Default")
      (node (ref "R66") (pin "2") (pinfunction "2_2") (pintype "passive"))
      (node (ref "U16") (pin "L8") (pinfunction "ZQ_L8") (pintype "passive"))
    )
    (net (code "54") (name "unconnected-(U16-NC-PadJ1)") (class "Default")
      (node (ref "U16") (pin "J1") (pinfunction "NC_J1") (pintype "passive+no_connect"))
    )
    (net (code "55") (name "unconnected-(U16-NC-PadJ9)") (class "Default")
      (node (ref "U16") (pin "J9") (pinfunction "NC_J9") (pintype "passive+no_connect"))
    )
    (net (code "56") (name "unconnected-(U16-NC-PadL1)") (class "Default")
      (node (ref "U16") (pin "L1") (pinfunction "NC_L1") (pintype "passive+no_connect"))
    )
    (net (code "57") (name "unconnected-(U16-NC-PadL9)") (class "Default")
      (node (ref "U16") (pin "L9") (pinfunction "NC_L9") (pintype "passive+no_connect"))
    )
    (net (code "58") (name "unconnected-(U16-NC-PadM7)") (class "Default")
      (node (ref "U16") (pin "M7") (pinfunction "NC_M7") (pintype "passive+no_connect"))
    )
    (net (code "59") (name "unconnected-(U16-NC-PadT7)") (class "Default")
      (node (ref "U16") (pin "T7") (pinfunction "NC_T7") (pintype "passive+no_connect"))
    )
  )
)
